# musical-wheelchair.net
KiCad netlist of a schematic drawn in EAGLE
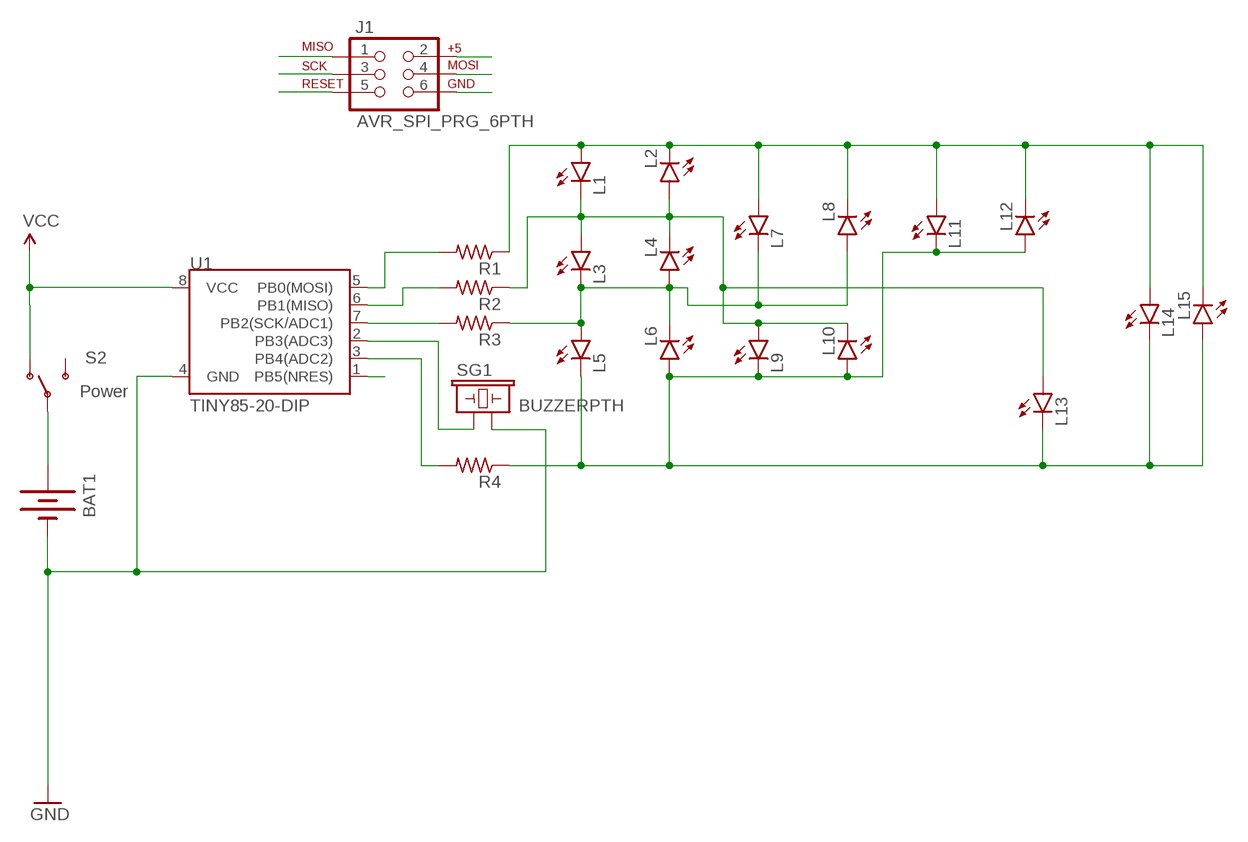
[diagram p0: schematic, sheet 1]

(export (version "E")
  (design (tool "Eeschema 10.0.6"))
  (components
    (comp (ref "BAT1")
      (value "BATTERY20PTH")
      (footprint "eagle-import:BATTCOM_20MM_PTH")
      (libsource (lib "eagle-import") (part "BATTERY20PTH"))
    )
    (comp (ref "J1")
      (value "AVR_SPI_PRG_6PTH")
      (footprint "eagle-import:2X3")
      (libsource (lib "eagle-import") (part "AVR_SPI_PRG_6PTH"))
    )
    (comp (ref "L1")
      (value "LED5MM")
      (footprint "eagle-import:LED5MM")
      (libsource (lib "eagle-import") (part "LED5MM"))
    )
    (comp (ref "L2")
      (value "LED5MM")
      (footprint "eagle-import:LED5MM")
      (libsource (lib "eagle-import") (part "LED5MM"))
    )
    (comp (ref "L3")
      (value "LED5MM")
      (footprint "eagle-import:LED5MM")
      (libsource (lib "eagle-import") (part "LED5MM"))
    )
    (comp (ref "L4")
      (value "LED5MM")
      (footprint "eagle-import:LED5MM")
      (libsource (lib "eagle-import") (part "LED5MM"))
    )
    (comp (ref "L5")
      (value "LED5MM")
      (footprint "eagle-import:LED5MM")
      (libsource (lib "eagle-import") (part "LED5MM"))
    )
    (comp (ref "L6")
      (value "LED5MM")
      (footprint "eagle-import:LED5MM")
      (libsource (lib "eagle-import") (part "LED5MM"))
    )
    (comp (ref "L7")
      (value "LED5MM")
      (footprint "eagle-import:LED5MM")
      (libsource (lib "eagle-import") (part "LED5MM"))
    )
    (comp (ref "L8")
      (value "LED5MM")
      (footprint "eagle-import:LED5MM")
      (libsource (lib "eagle-import") (part "LED5MM"))
    )
    (comp (ref "L9")
      (value "LED5MM")
      (footprint "eagle-import:LED5MM")
      (libsource (lib "eagle-import") (part "LED5MM"))
    )
    (comp (ref "L10")
      (value "LED5MM")
      (footprint "eagle-import:LED5MM")
      (libsource (lib "eagle-import") (part "LED5MM"))
    )
    (comp (ref "L11")
      (value "LED5MM")
      (footprint "eagle-import:LED5MM")
      (libsource (lib "eagle-import") (part "LED5MM"))
    )
    (comp (ref "L12")
      (value "LED5MM")
      (footprint "eagle-import:LED5MM")
      (libsource (lib "eagle-import") (part "LED5MM"))
    )
    (comp (ref "L13")
      (value "LED5MM")
      (footprint "eagle-import:LED5MM")
      (libsource (lib "eagle-import") (part "LED5MM"))
    )
    (comp (ref "L14")
      (value "LED5MM")
      (footprint "eagle-import:LED5MM")
      (libsource (lib "eagle-import") (part "LED5MM"))
    )
    (comp (ref "L15")
      (value "LED5MM")
      (footprint "eagle-import:LED5MM")
      (libsource (lib "eagle-import") (part "LED5MM"))
    )
    (comp (ref "R1")
      (value "R-US_0204/5")
      (footprint "eagle-import:0204_5")
      (libsource (lib "eagle-import") (part "R-US_0204/5"))
    )
    (comp (ref "R2")
      (value "R-US_0204/5")
      (footprint "eagle-import:0204_5")
      (libsource (lib "eagle-import") (part "R-US_0204/5"))
    )
    (comp (ref "R3")
      (value "R-US_0204/5")
      (footprint "eagle-import:0204_5")
      (libsource (lib "eagle-import") (part "R-US_0204/5"))
    )
    (comp (ref "R4")
      (value "R-US_0204/5")
      (footprint "eagle-import:0204_5")
      (libsource (lib "eagle-import") (part "R-US_0204/5"))
    )
    (comp (ref "S2")
      (value "Power")
      (footprint "eagle-import:SWITCH-SPDT")
      (libsource (lib "eagle-import") (part "SWITCH-SPDTPTH"))
    )
    (comp (ref "SG1")
      (value "BUZZERPTH")
      (footprint "eagle-import:BUZZER-12MM")
      (libsource (lib "eagle-import") (part "BUZZERPTH"))
    )
    (comp (ref "U1")
      (value "TINY85-20-DIP")
      (footprint "eagle-import:DIP08")
      (libsource (lib "eagle-import") (part "ATTINY45TINY85-20-DIP"))
    )
  )
  (nets
    (net (code "1") (name "/MISO") (class "Default")
      (node (ref "J1") (pin "1") (pinfunction "1_1") (pintype "passive"))
      (node (ref "R2") (pin "2") (pinfunction "2_2") (pintype "passive"))
      (node (ref "U1") (pin "6") (pinfunction "PB1(MISO)_6") (pintype "bidirectional"))
    )
    (net (code "2") (name "/MOSI") (class "Default")
      (node (ref "J1") (pin "4") (pinfunction "4_4") (pintype "passive"))
      (node (ref "R1") (pin "2") (pinfunction "2_2") (pintype "passive"))
      (node (ref "U1") (pin "5") (pinfunction "PB0(MOSI)_5") (pintype "bidirectional"))
    )
    (net (code "3") (name "/RST") (class "Default")
      (node (ref "J1") (pin "5") (pinfunction "5_5") (pintype "passive"))
      (node (ref "U1") (pin "1") (pinfunction "PB5(NRES)_1") (pintype "bidirectional"))
    )
    (net (code "4") (name "/SCK") (class "Default")
      (node (ref "J1") (pin "3") (pinfunction "3_3") (pintype "passive"))
      (node (ref "R3") (pin "2") (pinfunction "2_2") (pintype "passive"))
      (node (ref "U1") (pin "7") (pinfunction "PB2(SCK/ADC1)_7") (pintype "bidirectional"))
    )
    (net (code "5") (name "GND") (class "Default")
      (node (ref "BAT1") (pin "2") (pinfunction "-_2") (pintype "power_in"))
      (node (ref "J1") (pin "6") (pinfunction "6_6") (pintype "passive"))
      (node (ref "SG1") (pin "-") (pinfunction "2_-") (pintype "passive"))
      (node (ref "U1") (pin "4") (pinfunction "GND_4") (pintype "bidirectional"))
    )
    (net (code "6") (name "Net-(BAT1-+)") (class "Default")
      (node (ref "BAT1") (pin "1") (pinfunction "+_1") (pintype "power_in"))
      (node (ref "S2") (pin "2") (pinfunction "P_2") (pintype "passive"))
    )
    (net (code "7") (name "Net-(L1-C)") (class "Default")
      (node (ref "L1") (pin "K") (pinfunction "C_K") (pintype "passive"))
      (node (ref "L10") (pin "K") (pinfunction "C_K") (pintype "passive"))
      (node (ref "L13") (pin "A") (pinfunction "A_A") (pintype "passive"))
      (node (ref "L2") (pin "A") (pinfunction "A_A") (pintype "passive"))
      (node (ref "L3") (pin "A") (pinfunction "A_A") (pintype "passive"))
      (node (ref "L4") (pin "K") (pinfunction "C_K") (pintype "passive"))
      (node (ref "L9") (pin "A") (pinfunction "A_A") (pintype "passive"))
      (node (ref "R2") (pin "1") (pinfunction "1_1") (pintype "passive"))
    )
    (net (code "8") (name "Net-(L3-C)") (class "Default")
      (node (ref "L3") (pin "K") (pinfunction "C_K") (pintype "passive"))
      (node (ref "L4") (pin "A") (pinfunction "A_A") (pintype "passive"))
      (node (ref "L5") (pin "A") (pinfunction "A_A") (pintype "passive"))
      (node (ref "L6") (pin "K") (pinfunction "C_K") (pintype "passive"))
      (node (ref "L7") (pin "K") (pinfunction "C_K") (pintype "passive"))
      (node (ref "L8") (pin "A") (pinfunction "A_A") (pintype "passive"))
      (node (ref "R3") (pin "1") (pinfunction "1_1") (pintype "passive"))
    )
    (net (code "9") (name "Net-(L11-C)") (class "Default")
      (node (ref "L10") (pin "A") (pinfunction "A_A") (pintype "passive"))
      (node (ref "L11") (pin "K") (pinfunction "C_K") (pintype "passive"))
      (node (ref "L12") (pin "A") (pinfunction "A_A") (pintype "passive"))
      (node (ref "L13") (pin "K") (pinfunction "C_K") (pintype "passive"))
      (node (ref "L14") (pin "K") (pinfunction "C_K") (pintype "passive"))
      (node (ref "L15") (pin "A") (pinfunction "A_A") (pintype "passive"))
      (node (ref "L5") (pin "K") (pinfunction "C_K") (pintype "passive"))
      (node (ref "L6") (pin "A") (pinfunction "A_A") (pintype "passive"))
      (node (ref "L9") (pin "K") (pinfunction "C_K") (pintype "passive"))
      (node (ref "R4") (pin "1") (pinfunction "1_1") (pintype "passive"))
    )
    (net (code "10") (name "Net-(L12-C)") (class "Default")
      (node (ref "L1") (pin "A") (pinfunction "A_A") (pintype "passive"))
      (node (ref "L11") (pin "A") (pinfunction "A_A") (pintype "passive"))
      (node (ref "L12") (pin "K") (pinfunction "C_K") (pintype "passive"))
      (node (ref "L14") (pin "A") (pinfunction "A_A") (pintype "passive"))
      (node (ref "L15") (pin "K") (pinfunction "C_K") (pintype "passive"))
      (node (ref "L2") (pin "K") (pinfunction "C_K") (pintype "passive"))
      (node (ref "L7") (pin "A") (pinfunction "A_A") (pintype "passive"))
      (node (ref "L8") (pin "K") (pinfunction "C_K") (pintype "passive"))
      (node (ref "R1") (pin "1") (pinfunction "1_1") (pintype "passive"))
    )
    (net (code "11") (name "Net-(SG1-1)") (class "Default")
      (node (ref "SG1") (pin "+") (pinfunction "1_+") (pintype "passive"))
      (node (ref "U1") (pin "2") (pinfunction "PB3(ADC3)_2") (pintype "bidirectional"))
    )
    (net (code "12") (name "Net-(U1-PB4(ADC2))") (class "Default")
      (node (ref "R4") (pin "2") (pinfunction "2_2") (pintype "passive"))
      (node (ref "U1") (pin "3") (pinfunction "PB4(ADC2)_3") (pintype "bidirectional"))
    )
    (net (code "13") (name "VCC") (class "Default")
      (node (ref "J1") (pin "2") (pinfunction "2_2") (pintype "passive"))
      (node (ref "S2") (pin "1") (pinfunction "O_1") (pintype "passive"))
      (node (ref "U1") (pin "8") (pinfunction "VCC_8") (pintype "bidirectional"))
    )
    (net (code "14") (name "unconnected-(S2-S-Pad3)") (class "Default")
      (node (ref "S2") (pin "3") (pinfunction "S_3") (pintype "passive"))
    )
  )
)
